# SCH_Flight-Computer-V4_2024-07-20.net
KiCad netlist of a schematic drawn in EasyEDA
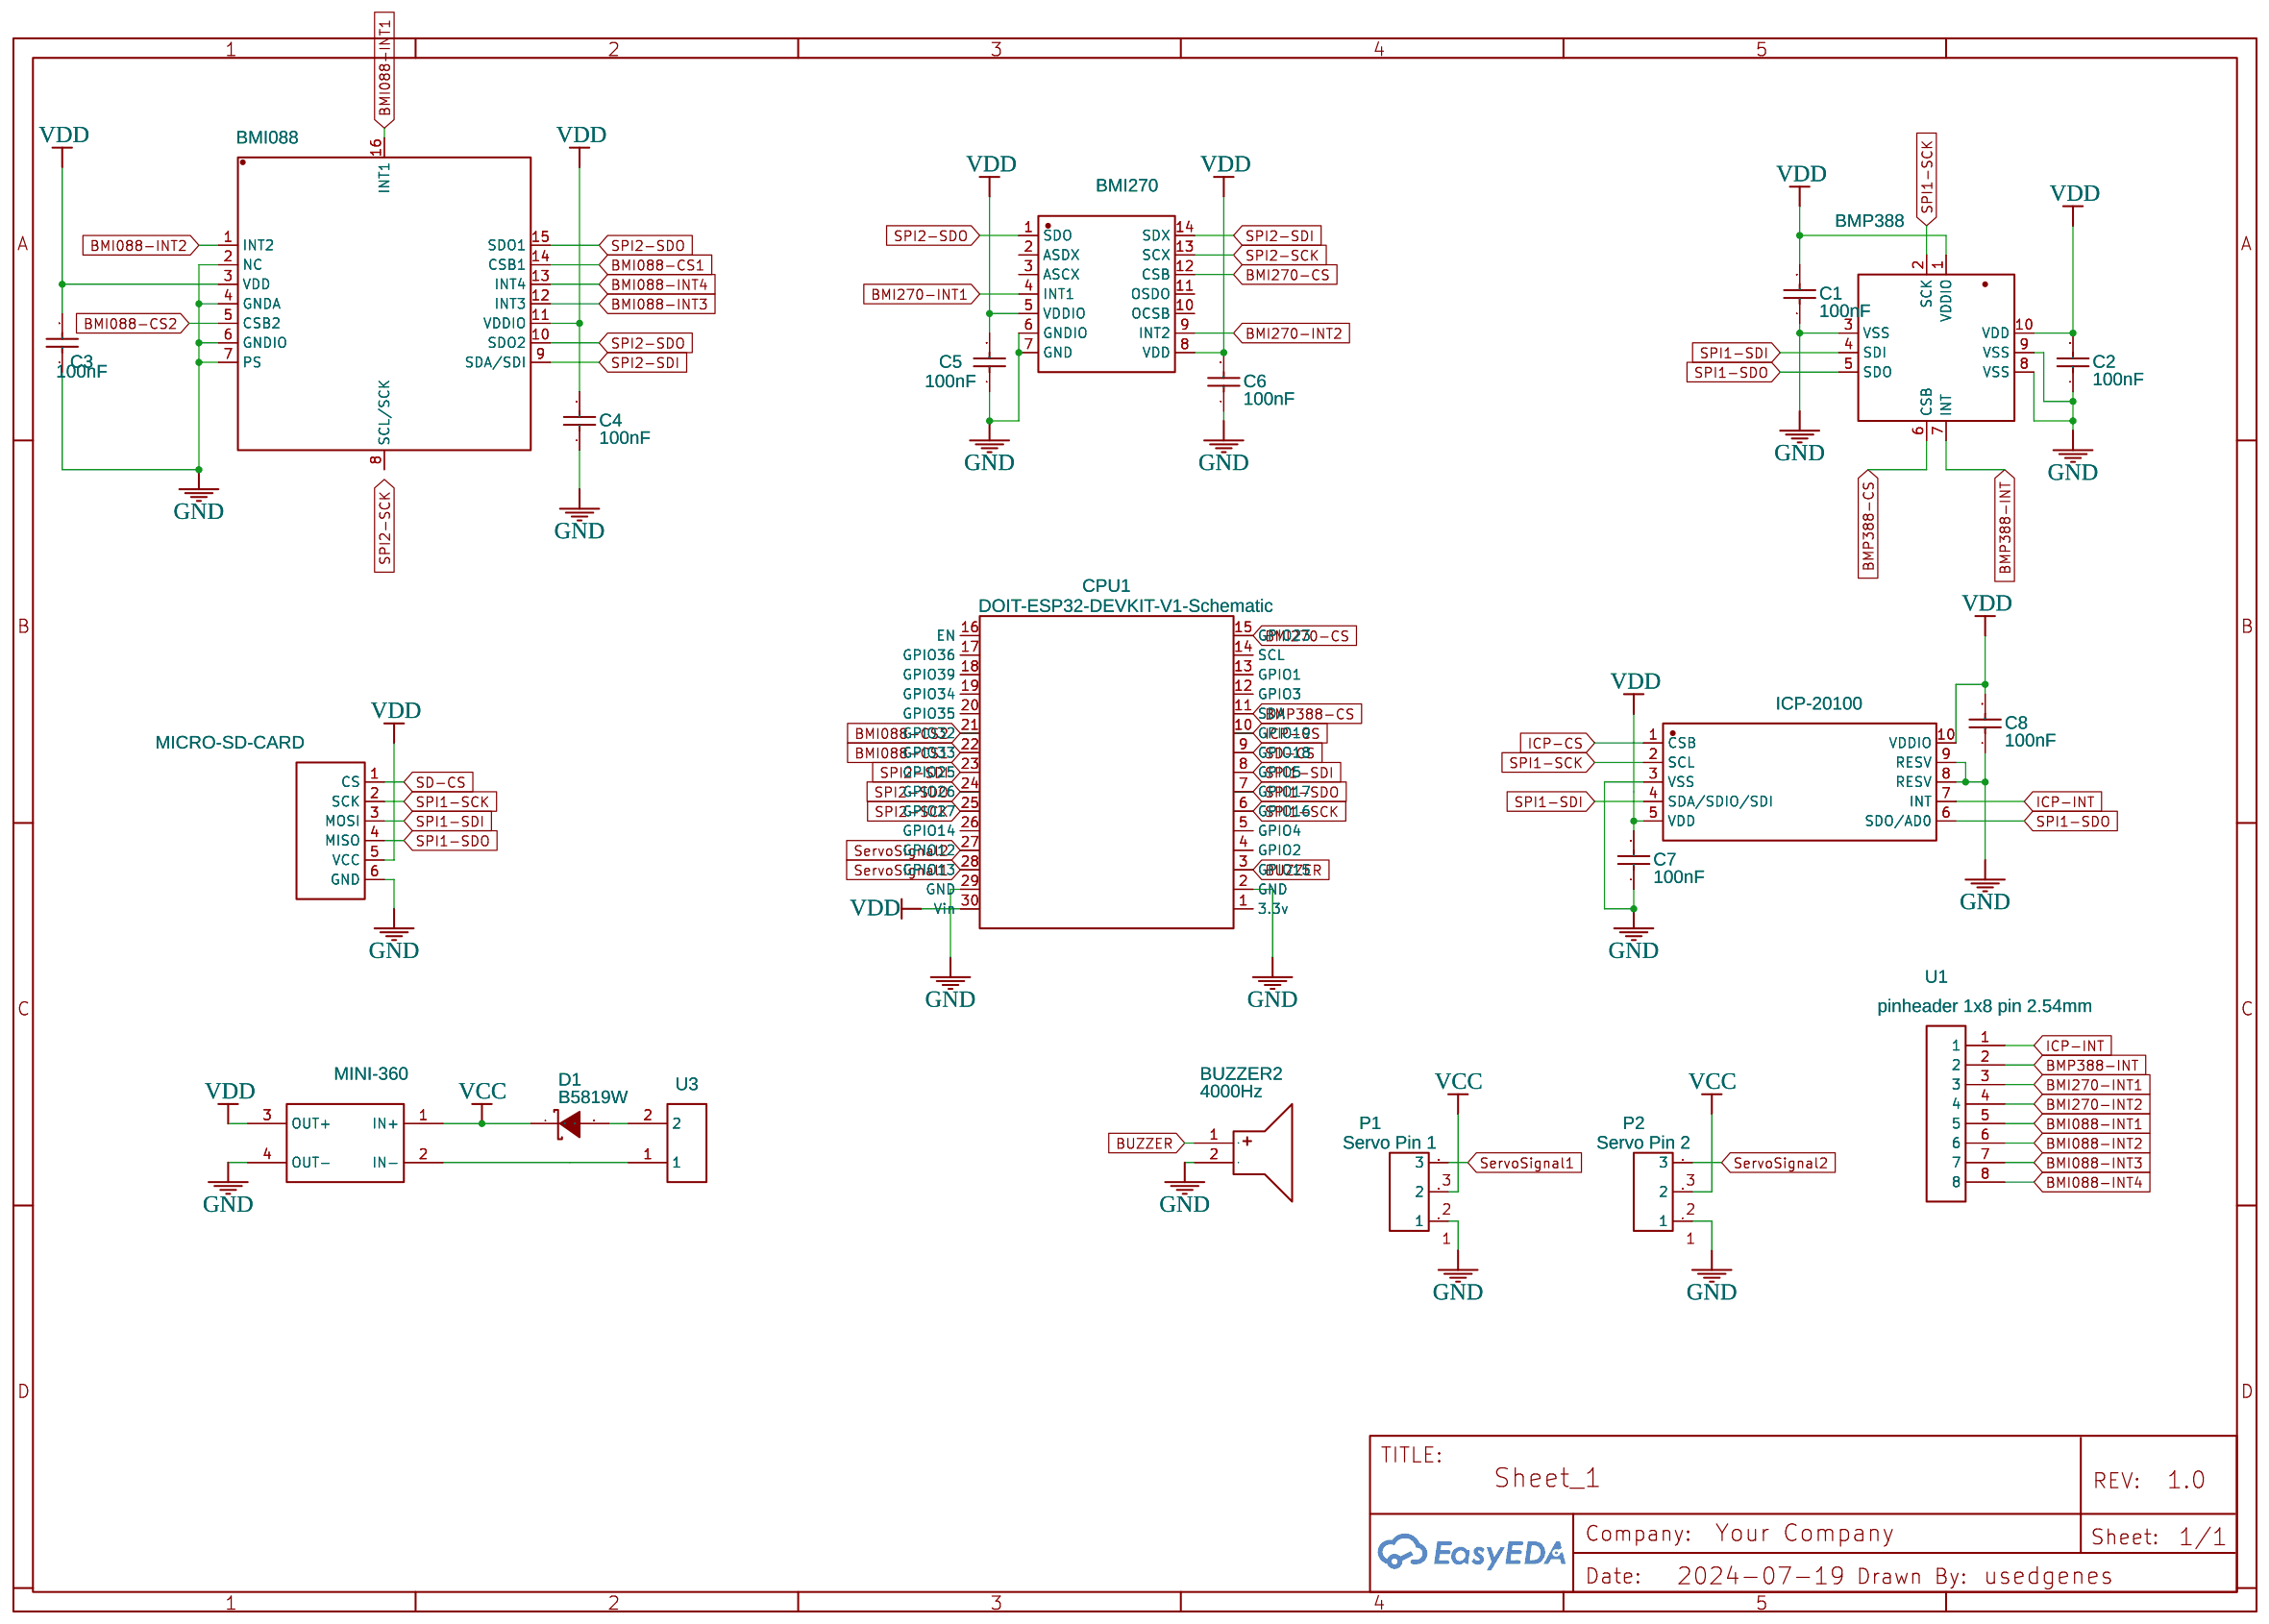
[diagram p0: schematic sheet]

(export (version "E")
  (design (tool "Eeschema 10.0.6"))
  (components
    (comp (ref "BMI088")
      (value "BMI088")
      (fields (field (name "Manufacturer") "Bosch(博世)"))
      (libsource (lib "") (part "BMI088"))
    )
    (comp (ref "BMI270")
      (value "BMI270")
      (fields (field (name "Manufacturer") "Bosch(博世)"))
      (libsource (lib "") (part "BMI270"))
    )
    (comp (ref "BMP388")
      (value "BMP388")
      (fields (field (name "Manufacturer") "Bosch(博世)"))
      (libsource (lib "") (part "BMP388"))
    )
    (comp (ref "BUZZER2")
      (value "4000Hz")
      (fields
        (field (name "Manufacturer Part") "SKY-1475-0540-45P7.6")
        (field (name "Manufacturer") "S&S(海旭)")
      )
      (libsource (lib "") (part "SKY-1475-0540-45P7.6"))
    )
    (comp (ref "C1")
      (value "100nF")
      (fields
        (field (name "Manufacturer Part") "CL05B104KO5NNNC")
        (field (name "Manufacturer") "SAMSUNG(三星)")
      )
      (libsource (lib "") (part "CL05B104KO5NNNC"))
    )
    (comp (ref "C2")
      (value "100nF")
      (fields
        (field (name "Manufacturer Part") "CL05B104KO5NNNC")
        (field (name "Manufacturer") "SAMSUNG(三星)")
      )
      (libsource (lib "") (part "CL05B104KO5NNNC"))
    )
    (comp (ref "C3")
      (value "100nF")
      (fields
        (field (name "Manufacturer Part") "CL05B104KO5NNNC")
        (field (name "Manufacturer") "SAMSUNG(三星)")
      )
      (libsource (lib "") (part "CL05B104KO5NNNC"))
    )
    (comp (ref "C4")
      (value "100nF")
      (fields
        (field (name "Manufacturer Part") "CL05B104KO5NNNC")
        (field (name "Manufacturer") "SAMSUNG(三星)")
      )
      (libsource (lib "") (part "CL05B104KO5NNNC"))
    )
    (comp (ref "C5")
      (value "100nF")
      (fields
        (field (name "Manufacturer Part") "CL05B104KO5NNNC")
        (field (name "Manufacturer") "SAMSUNG(三星)")
      )
      (libsource (lib "") (part "CL05B104KO5NNNC"))
    )
    (comp (ref "C6")
      (value "100nF")
      (fields
        (field (name "Manufacturer Part") "CL05B104KO5NNNC")
        (field (name "Manufacturer") "SAMSUNG(三星)")
      )
      (libsource (lib "") (part "CL05B104KO5NNNC"))
    )
    (comp (ref "C7")
      (value "100nF")
      (fields
        (field (name "Manufacturer Part") "CL05B104KO5NNNC")
        (field (name "Manufacturer") "SAMSUNG(三星)")
      )
      (libsource (lib "") (part "CL05B104KO5NNNC"))
    )
    (comp (ref "C8")
      (value "100nF")
      (fields
        (field (name "Manufacturer Part") "CL05B104KO5NNNC")
        (field (name "Manufacturer") "SAMSUNG(三星)")
      )
      (libsource (lib "") (part "CL05B104KO5NNNC"))
    )
    (comp (ref "CPU1")
      (value "DOIT-ESP32-DEVKIT-V1-Schematic")
      (fields (field (name "Manufacturer Part") "NONE"))
      (libsource (lib "") (part "DOIT-ESP32-DEVKIT-V1-Schematic"))
    )
    (comp (ref "D1")
      (value "B5819W")
      (fields (field (name "Manufacturer") "MDD(辰达半导体)"))
      (libsource (lib "") (part "B5819W"))
    )
    (comp (ref "ICP-20100")
      (value "ICP-20100")
      (fields (field (name "Manufacturer") "TDK"))
      (libsource (lib "") (part "ICP-20100"))
    )
    (comp (ref "MICRO-SD-CARD") (value "MicroSDCardAdapter") (libsource (lib "") (part "MicroSDCardAdapter")))
    (comp (ref "MINI-360") (value "MINI-360") (libsource (lib "") (part "MINI-360")))
    (comp (ref "P1")
      (value "Servo Pin 1")
      (fields
        (field (name "Manufacturer Part") "Female headerHDR1X8-2.54")
        (field (name "Manufacturer") "BOOMELE")
      )
      (libsource (lib "") (part "HEADER PAD 3X RMM COPY"))
    )
    (comp (ref "P2")
      (value "Servo Pin 2")
      (fields
        (field (name "Manufacturer Part") "Female headerHDR1X8-2.54")
        (field (name "Manufacturer") "BOOMELE")
      )
      (libsource (lib "") (part "HEADER PAD 3X RMM COPY"))
    )
    (comp (ref "U1")
      (value "pinheader 1x8 pin 2.54mm")
      (fields (field (name "Manufacturer Part") "unknown"))
      (libsource (lib "") (part "pinheader 1x8 pin 2.54mm"))
    )
    (comp (ref "U3") (value "Power Pins") (libsource (lib "") (part "1X2")))
  )
  (nets
    (net (code "1") (name "BMI088-CS1") (class "Default")
      (node (ref "BMI088") (pin "14") (pinfunction "CSB1_14") (pintype "unspecified"))
      (node (ref "CPU1") (pin "22") (pinfunction "GPIO33_22") (pintype "unspecified"))
    )
    (net (code "2") (name "BMI088-CS2") (class "Default")
      (node (ref "BMI088") (pin "5") (pinfunction "CSB2_5") (pintype "unspecified"))
      (node (ref "CPU1") (pin "21") (pinfunction "GPIO32_21") (pintype "unspecified"))
    )
    (net (code "3") (name "BMI088-INT1") (class "Default")
      (node (ref "BMI088") (pin "16") (pinfunction "INT1_16") (pintype "unspecified"))
      (node (ref "U1") (pin "5") (pinfunction "5_5") (pintype "unspecified"))
    )
    (net (code "4") (name "BMI088-INT2") (class "Default")
      (node (ref "BMI088") (pin "1") (pinfunction "INT2_1") (pintype "unspecified"))
      (node (ref "U1") (pin "6") (pinfunction "6_6") (pintype "unspecified"))
    )
    (net (code "5") (name "BMI088-INT3") (class "Default")
      (node (ref "BMI088") (pin "12") (pinfunction "INT3_12") (pintype "unspecified"))
      (node (ref "U1") (pin "7") (pinfunction "7_7") (pintype "unspecified"))
    )
    (net (code "6") (name "BMI088-INT4") (class "Default")
      (node (ref "BMI088") (pin "13") (pinfunction "INT4_13") (pintype "unspecified"))
      (node (ref "U1") (pin "8") (pinfunction "8_8") (pintype "unspecified"))
    )
    (net (code "7") (name "BMI270-CS") (class "Default")
      (node (ref "BMI270") (pin "12") (pinfunction "CSB_12") (pintype "unspecified"))
      (node (ref "CPU1") (pin "15") (pinfunction "GPIO23_15") (pintype "unspecified"))
    )
    (net (code "8") (name "BMI270-INT1") (class "Default")
      (node (ref "BMI270") (pin "4") (pinfunction "INT1_4") (pintype "unspecified"))
      (node (ref "U1") (pin "3") (pinfunction "3_3") (pintype "unspecified"))
    )
    (net (code "9") (name "BMI270-INT2") (class "Default")
      (node (ref "BMI270") (pin "9") (pinfunction "INT2_9") (pintype "unspecified"))
      (node (ref "U1") (pin "4") (pinfunction "4_4") (pintype "unspecified"))
    )
    (net (code "10") (name "BMP388-CS") (class "Default")
      (node (ref "BMP388") (pin "6") (pinfunction "CSB_6") (pintype "unspecified"))
      (node (ref "CPU1") (pin "11") (pinfunction "SDA_11") (pintype "unspecified"))
    )
    (net (code "11") (name "BMP388-INT") (class "Default")
      (node (ref "BMP388") (pin "7") (pinfunction "INT_7") (pintype "unspecified"))
      (node (ref "U1") (pin "2") (pinfunction "2_2") (pintype "unspecified"))
    )
    (net (code "12") (name "BUZZER") (class "Default")
      (node (ref "BUZZER2") (pin "1") (pinfunction "+_1") (pintype "unspecified"))
      (node (ref "CPU1") (pin "3") (pinfunction "GPIO15_3") (pintype "unspecified"))
    )
    (net (code "13") (name "GND") (class "Default")
      (node (ref "BMI088") (pin "2") (pinfunction "NC_2") (pintype "unspecified"))
      (node (ref "BMI088") (pin "4") (pinfunction "GNDA_4") (pintype "unspecified"))
      (node (ref "BMI088") (pin "6") (pinfunction "GNDIO_6") (pintype "unspecified"))
      (node (ref "BMI088") (pin "7") (pinfunction "PS_7") (pintype "unspecified"))
      (node (ref "BMI270") (pin "6") (pinfunction "GNDIO_6") (pintype "unspecified"))
      (node (ref "BMI270") (pin "7") (pinfunction "GND_7") (pintype "unspecified"))
      (node (ref "BMP388") (pin "3") (pinfunction "VSS_3") (pintype "unspecified"))
      (node (ref "BMP388") (pin "8") (pinfunction "VSS_8") (pintype "unspecified"))
      (node (ref "BMP388") (pin "9") (pinfunction "VSS_9") (pintype "unspecified"))
      (node (ref "BUZZER2") (pin "2") (pinfunction "-_2") (pintype "unspecified"))
      (node (ref "C1") (pin "1") (pinfunction "1_1") (pintype "input"))
      (node (ref "C2") (pin "1") (pinfunction "1_1") (pintype "input"))
      (node (ref "C3") (pin "1") (pinfunction "1_1") (pintype "input"))
      (node (ref "C4") (pin "1") (pinfunction "1_1") (pintype "input"))
      (node (ref "C5") (pin "1") (pinfunction "1_1") (pintype "input"))
      (node (ref "C6") (pin "1") (pinfunction "1_1") (pintype "input"))
      (node (ref "C7") (pin "1") (pinfunction "1_1") (pintype "input"))
      (node (ref "C8") (pin "1") (pinfunction "1_1") (pintype "input"))
      (node (ref "CPU1") (pin "2") (pinfunction "GND_2") (pintype "unspecified"))
      (node (ref "CPU1") (pin "29") (pinfunction "GND_29") (pintype "unspecified"))
      (node (ref "ICP-20100") (pin "3") (pinfunction "VSS_3") (pintype "unspecified"))
      (node (ref "ICP-20100") (pin "8") (pinfunction "RESV_8") (pintype "unspecified"))
      (node (ref "ICP-20100") (pin "9") (pinfunction "RESV_9") (pintype "unspecified"))
      (node (ref "MICRO-SD-CARD") (pin "6") (pinfunction "GND_6") (pintype "passive"))
      (node (ref "MINI-360") (pin "4") (pinfunction "OUT-_4") (pintype "unspecified"))
      (node (ref "P1") (pin "1") (pinfunction "1_1") (pintype "unspecified"))
      (node (ref "P2") (pin "1") (pinfunction "1_1") (pintype "unspecified"))
    )
    (net (code "14") (name "ICP-CS") (class "Default")
      (node (ref "CPU1") (pin "10") (pinfunction "GPIO19_10") (pintype "unspecified"))
      (node (ref "ICP-20100") (pin "1") (pinfunction "CSB_1") (pintype "unspecified"))
    )
    (net (code "15") (name "ICP-INT") (class "Default")
      (node (ref "ICP-20100") (pin "7") (pinfunction "INT_7") (pintype "unspecified"))
      (node (ref "U1") (pin "1") (pinfunction "1_1") (pintype "unspecified"))
    )
    (net (code "16") (name "Net-(D1-A)") (class "Default")
      (node (ref "D1") (pin "2") (pinfunction "A_2") (pintype "unspecified"))
      (node (ref "U3") (pin "2") (pinfunction "2_2") (pintype "unspecified"))
    )
    (net (code "17") (name "Net-(MINI-360-IN-)") (class "Default")
      (node (ref "MINI-360") (pin "2") (pinfunction "IN-_2") (pintype "unspecified"))
      (node (ref "U3") (pin "1") (pinfunction "1_1") (pintype "unspecified"))
    )
    (net (code "18") (name "SD-CS") (class "Default")
      (node (ref "CPU1") (pin "9") (pinfunction "GPIO18_9") (pintype "unspecified"))
      (node (ref "MICRO-SD-CARD") (pin "1") (pinfunction "CS_1") (pintype "bidirectional"))
    )
    (net (code "19") (name "SPI1-SCK") (class "Default")
      (node (ref "BMP388") (pin "2") (pinfunction "SCK_2") (pintype "unspecified"))
      (node (ref "CPU1") (pin "6") (pinfunction "GPIO16_6") (pintype "unspecified"))
      (node (ref "ICP-20100") (pin "2") (pinfunction "SCL_2") (pintype "unspecified"))
      (node (ref "MICRO-SD-CARD") (pin "2") (pinfunction "SCK_2") (pintype "bidirectional"))
    )
    (net (code "20") (name "SPI1-SDI") (class "Default")
      (node (ref "BMP388") (pin "4") (pinfunction "SDI_4") (pintype "unspecified"))
      (node (ref "CPU1") (pin "8") (pinfunction "GPIO5_8") (pintype "unspecified"))
      (node (ref "ICP-20100") (pin "4") (pinfunction "SDA/SDIO/SDI_4") (pintype "unspecified"))
      (node (ref "MICRO-SD-CARD") (pin "3") (pinfunction "MOSI_3") (pintype "passive"))
    )
    (net (code "21") (name "SPI1-SDO") (class "Default")
      (node (ref "BMP388") (pin "5") (pinfunction "SDO_5") (pintype "unspecified"))
      (node (ref "CPU1") (pin "7") (pinfunction "GPIO17_7") (pintype "unspecified"))
      (node (ref "ICP-20100") (pin "6") (pinfunction "SDO/AD0_6") (pintype "unspecified"))
      (node (ref "MICRO-SD-CARD") (pin "4") (pinfunction "MISO_4") (pintype "bidirectional"))
    )
    (net (code "22") (name "SPI2-SCK") (class "Default")
      (node (ref "BMI270") (pin "13") (pinfunction "SCX_13") (pintype "unspecified"))
      (node (ref "CPU1") (pin "25") (pinfunction "GPIO27_25") (pintype "unspecified"))
    )
    (net (code "23") (name "SPI2-SDI") (class "Default")
      (node (ref "BMI088") (pin "9") (pinfunction "SDA/SDI_9") (pintype "unspecified"))
      (node (ref "BMI270") (pin "14") (pinfunction "SDX_14") (pintype "unspecified"))
      (node (ref "CPU1") (pin "23") (pinfunction "GPIO25_23") (pintype "unspecified"))
    )
    (net (code "24") (name "SPI2-SDO") (class "Default")
      (node (ref "BMI088") (pin "10") (pinfunction "SDO2_10") (pintype "unspecified"))
      (node (ref "BMI088") (pin "15") (pinfunction "SDO1_15") (pintype "unspecified"))
      (node (ref "BMI270") (pin "1") (pinfunction "SDO_1") (pintype "unspecified"))
      (node (ref "CPU1") (pin "24") (pinfunction "GPIO26_24") (pintype "unspecified"))
    )
    (net (code "25") (name "ServoSignal1") (class "Default")
      (node (ref "CPU1") (pin "28") (pinfunction "GPIO13_28") (pintype "unspecified"))
      (node (ref "P1") (pin "3") (pinfunction "3_3") (pintype "unspecified"))
    )
    (net (code "26") (name "ServoSignal2") (class "Default")
      (node (ref "CPU1") (pin "27") (pinfunction "GPIO12_27") (pintype "unspecified"))
      (node (ref "P2") (pin "3") (pinfunction "3_3") (pintype "unspecified"))
    )
    (net (code "27") (name "VCC") (class "Default")
      (node (ref "D1") (pin "1") (pinfunction "K_1") (pintype "unspecified"))
      (node (ref "MINI-360") (pin "1") (pinfunction "IN+_1") (pintype "unspecified"))
      (node (ref "P1") (pin "2") (pinfunction "2_2") (pintype "unspecified"))
      (node (ref "P2") (pin "2") (pinfunction "2_2") (pintype "unspecified"))
    )
    (net (code "28") (name "VDD") (class "Default")
      (node (ref "BMI088") (pin "11") (pinfunction "VDDIO_11") (pintype "unspecified"))
      (node (ref "BMI088") (pin "3") (pinfunction "VDD_3") (pintype "unspecified"))
      (node (ref "BMI270") (pin "5") (pinfunction "VDDIO_5") (pintype "unspecified"))
      (node (ref "BMI270") (pin "8") (pinfunction "VDD_8") (pintype "unspecified"))
      (node (ref "BMP388") (pin "1") (pinfunction "VDDIO_1") (pintype "unspecified"))
      (node (ref "BMP388") (pin "10") (pinfunction "VDD_10") (pintype "unspecified"))
      (node (ref "C1") (pin "2") (pinfunction "2_2") (pintype "input"))
      (node (ref "C2") (pin "2") (pinfunction "2_2") (pintype "input"))
      (node (ref "C3") (pin "2") (pinfunction "2_2") (pintype "input"))
      (node (ref "C4") (pin "2") (pinfunction "2_2") (pintype "input"))
      (node (ref "C5") (pin "2") (pinfunction "2_2") (pintype "input"))
      (node (ref "C6") (pin "2") (pinfunction "2_2") (pintype "input"))
      (node (ref "C7") (pin "2") (pinfunction "2_2") (pintype "input"))
      (node (ref "C8") (pin "2") (pinfunction "2_2") (pintype "input"))
      (node (ref "CPU1") (pin "30") (pinfunction "Vin_30") (pintype "unspecified"))
      (node (ref "ICP-20100") (pin "10") (pinfunction "VDDIO_10") (pintype "unspecified"))
      (node (ref "ICP-20100") (pin "5") (pinfunction "VDD_5") (pintype "unspecified"))
      (node (ref "MICRO-SD-CARD") (pin "5") (pinfunction "VCC_5") (pintype "passive"))
      (node (ref "MINI-360") (pin "3") (pinfunction "OUT+_3") (pintype "unspecified"))
    )
    (net (code "29") (name "unconnected-(BMI088-SCL{slash}SCK-Pad8)") (class "Default")
      (node (ref "BMI088") (pin "8") (pinfunction "SCL/SCK_8") (pintype "unspecified"))
    )
    (net (code "30") (name "unconnected-(BMI270-ASCX-Pad3)") (class "Default")
      (node (ref "BMI270") (pin "3") (pinfunction "ASCX_3") (pintype "unspecified"))
    )
    (net (code "31") (name "unconnected-(BMI270-ASDX-Pad2)") (class "Default")
      (node (ref "BMI270") (pin "2") (pinfunction "ASDX_2") (pintype "unspecified"))
    )
    (net (code "32") (name "unconnected-(BMI270-OCSB-Pad10)") (class "Default")
      (node (ref "BMI270") (pin "10") (pinfunction "OCSB_10") (pintype "unspecified"))
    )
    (net (code "33") (name "unconnected-(BMI270-OSDO-Pad11)") (class "Default")
      (node (ref "BMI270") (pin "11") (pinfunction "OSDO_11") (pintype "unspecified"))
    )
    (net (code "34") (name "unconnected-(CPU1-3.3v-Pad1)") (class "Default")
      (node (ref "CPU1") (pin "1") (pinfunction "3.3v_1") (pintype "unspecified"))
    )
    (net (code "35") (name "unconnected-(CPU1-EN-Pad16)") (class "Default")
      (node (ref "CPU1") (pin "16") (pinfunction "EN_16") (pintype "unspecified"))
    )
    (net (code "36") (name "unconnected-(CPU1-GPIO1-Pad13)") (class "Default")
      (node (ref "CPU1") (pin "13") (pinfunction "GPIO1_13") (pintype "unspecified"))
    )
    (net (code "37") (name "unconnected-(CPU1-GPIO2-Pad4)") (class "Default")
      (node (ref "CPU1") (pin "4") (pinfunction "GPIO2_4") (pintype "unspecified"))
    )
    (net (code "38") (name "unconnected-(CPU1-GPIO3-Pad12)") (class "Default")
      (node (ref "CPU1") (pin "12") (pinfunction "GPIO3_12") (pintype "unspecified"))
    )
    (net (code "39") (name "unconnected-(CPU1-GPIO4-Pad5)") (class "Default")
      (node (ref "CPU1") (pin "5") (pinfunction "GPIO4_5") (pintype "unspecified"))
    )
    (net (code "40") (name "unconnected-(CPU1-GPIO14-Pad26)") (class "Default")
      (node (ref "CPU1") (pin "26") (pinfunction "GPIO14_26") (pintype "unspecified"))
    )
    (net (code "41") (name "unconnected-(CPU1-GPIO34-Pad19)") (class "Default")
      (node (ref "CPU1") (pin "19") (pinfunction "GPIO34_19") (pintype "unspecified"))
    )
    (net (code "42") (name "unconnected-(CPU1-GPIO35-Pad20)") (class "Default")
      (node (ref "CPU1") (pin "20") (pinfunction "GPIO35_20") (pintype "unspecified"))
    )
    (net (code "43") (name "unconnected-(CPU1-GPIO36-Pad17)") (class "Default")
      (node (ref "CPU1") (pin "17") (pinfunction "GPIO36_17") (pintype "unspecified"))
    )
    (net (code "44") (name "unconnected-(CPU1-GPIO39-Pad18)") (class "Default")
      (node (ref "CPU1") (pin "18") (pinfunction "GPIO39_18") (pintype "unspecified"))
    )
    (net (code "45") (name "unconnected-(CPU1-SCL-Pad14)") (class "Default")
      (node (ref "CPU1") (pin "14") (pinfunction "SCL_14") (pintype "unspecified"))
    )
  )
)
